# oswietlenie.net
KiCad netlist of a schematic drawn in EAGLE
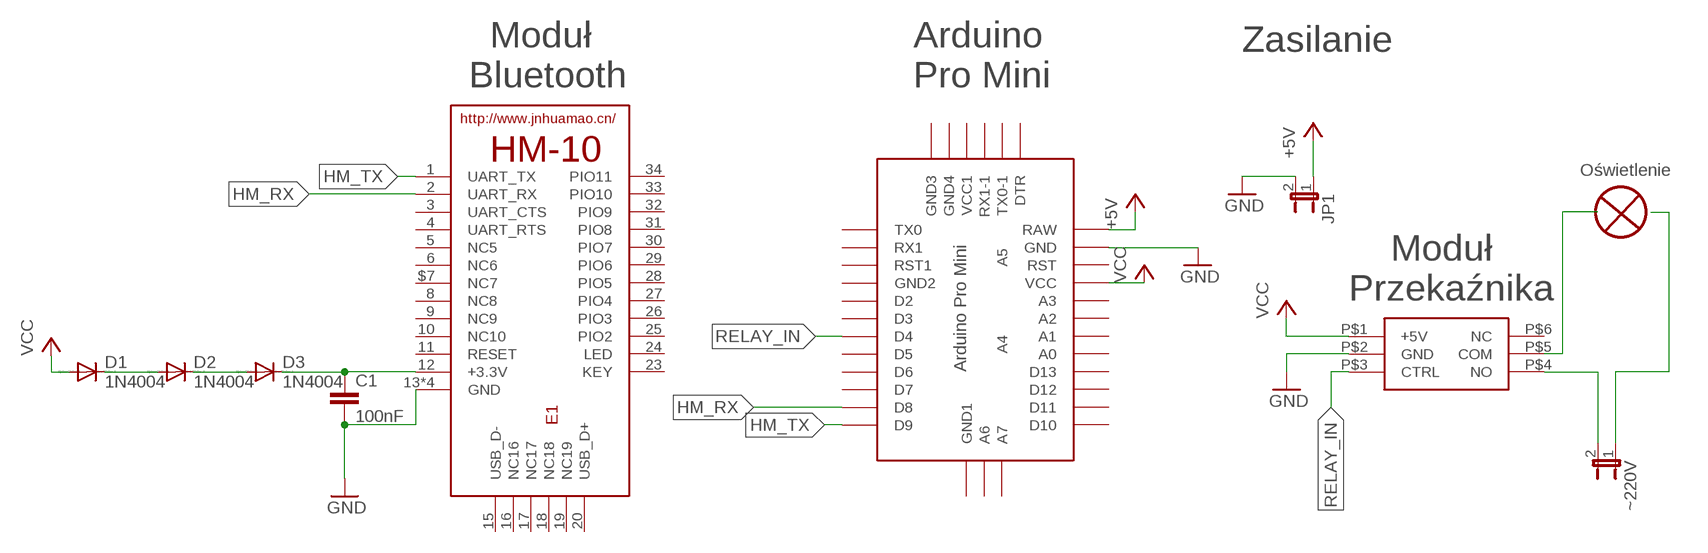
[diagram p0: schematic, sheet 1]

(export (version "E")
  (design (tool "Eeschema 10.0.6"))
  (components
    (comp (ref "C1")
      (value "100nF")
      (footprint "eagle-import:C025-024X044")
      (libsource (lib "eagle-import") (part "C-EU025-024X044"))
    )
    (comp (ref "D1")
      (value "1N4004")
      (footprint "eagle-import:DO41-10")
      (libsource (lib "eagle-import") (part "1N4004"))
    )
    (comp (ref "D2")
      (value "1N4004")
      (footprint "eagle-import:DO41-10")
      (libsource (lib "eagle-import") (part "1N4004"))
    )
    (comp (ref "D3")
      (value "1N4004")
      (footprint "eagle-import:DO41-10")
      (libsource (lib "eagle-import") (part "1N4004"))
    )
    (comp (ref "E1")
      (value "HM-10-BOARD")
      (footprint "eagle-import:26.9X13X2.2_BOARD")
      (libsource (lib "eagle-import") (part "HM-10-BOARD"))
    )
    (comp (ref "JP1")
      (value "JP1E")
      (footprint "eagle-import:JP1")
      (libsource (lib "eagle-import") (part "JP1E"))
    )
    (comp (ref "U$1")
      (value "ABK-PRO-MINI")
      (footprint "eagle-import:ABK-PRO-MINI")
      (libsource (lib "eagle-import") (part "ABK-PRO-MINI"))
    )
    (comp (ref "U$2")
      (value "G3VM-61E1")
      (footprint "eagle-import:G3VM-61E1")
      (libsource (lib "eagle-import") (part "G3VM-61E1"))
    )
    (comp (ref "~220V")
      (value "JP1E")
      (footprint "eagle-import:JP1")
      (libsource (lib "eagle-import") (part "JP1E"))
    )
  )
  (nets
    (net (code "1") (name "+5V") (class "Default")
      (node (ref "JP1") (pin "1") (pinfunction "1_1") (pintype "passive"))
      (node (ref "U$1") (pin "RAW") (pinfunction "RAW_RAW") (pintype "bidirectional"))
    )
    (net (code "2") (name "GND") (class "Default")
      (node (ref "C1") (pin "2") (pinfunction "2_2") (pintype "passive"))
      (node (ref "E1") (pin "13") (pinfunction "GND_13") (pintype "bidirectional"))
      (node (ref "E1") (pin "14") (pinfunction "GND_14") (pintype "bidirectional"))
      (node (ref "E1") (pin "21") (pinfunction "GND_21") (pintype "bidirectional"))
      (node (ref "E1") (pin "22") (pinfunction "GND_22") (pintype "bidirectional"))
      (node (ref "JP1") (pin "2") (pinfunction "2_2") (pintype "passive"))
      (node (ref "U$1") (pin "GND") (pinfunction "GND_GND") (pintype "bidirectional"))
      (node (ref "U$2") (pin "P$2") (pinfunction "GND_P$2") (pintype "bidirectional"))
    )
    (net (code "3") (name "HM_RX") (class "Default")
      (node (ref "E1") (pin "2") (pinfunction "UART_RX_2") (pintype "bidirectional"))
      (node (ref "U$1") (pin "D8") (pinfunction "D8_D8") (pintype "bidirectional"))
    )
    (net (code "4") (name "HM_TX") (class "Default")
      (node (ref "E1") (pin "1") (pinfunction "UART_TX_1") (pintype "bidirectional"))
      (node (ref "U$1") (pin "D9") (pinfunction "D9_D9") (pintype "bidirectional"))
    )
    (net (code "5") (name "Net-(D1-PadC)") (class "Default")
      (node (ref "D1") (pin "C") (pinfunction "C_C") (pintype "passive"))
      (node (ref "D2") (pin "A") (pinfunction "A_A") (pintype "passive"))
    )
    (net (code "6") (name "Net-(D2-PadC)") (class "Default")
      (node (ref "D2") (pin "C") (pinfunction "C_C") (pintype "passive"))
      (node (ref "D3") (pin "A") (pinfunction "A_A") (pintype "passive"))
    )
    (net (code "7") (name "Net-(E1-+3.3V)") (class "Default")
      (node (ref "C1") (pin "1") (pinfunction "1_1") (pintype "passive"))
      (node (ref "D3") (pin "C") (pinfunction "C_C") (pintype "passive"))
      (node (ref "E1") (pin "12") (pinfunction "+3.3V_12") (pintype "bidirectional"))
    )
    (net (code "8") (name "Net-(U$2-NO)") (class "Default")
      (node (ref "U$2") (pin "P$4") (pinfunction "NO_P$4") (pintype "bidirectional"))
      (node (ref "~220V") (pin "2") (pinfunction "2_2") (pintype "passive"))
    )
    (net (code "9") (name "RELAY_IN") (class "Default")
      (node (ref "U$1") (pin "D4") (pinfunction "D4_D4") (pintype "bidirectional"))
      (node (ref "U$2") (pin "P$3") (pinfunction "CTRL_P$3") (pintype "bidirectional"))
    )
    (net (code "10") (name "VCC") (class "Default")
      (node (ref "D1") (pin "A") (pinfunction "A_A") (pintype "passive"))
      (node (ref "U$1") (pin "VCC") (pinfunction "VCC_VCC") (pintype "bidirectional"))
      (node (ref "U$2") (pin "P$1") (pinfunction "+5V_P$1") (pintype "bidirectional"))
    )
    (net (code "11") (name "unconnected-(E1-KEY-Pad23)") (class "Default")
      (node (ref "E1") (pin "23") (pinfunction "KEY_23") (pintype "bidirectional"))
    )
    (net (code "12") (name "unconnected-(E1-LED-Pad24)") (class "Default")
      (node (ref "E1") (pin "24") (pinfunction "LED_24") (pintype "bidirectional"))
    )
    (net (code "13") (name "unconnected-(E1-NC5-Pad5)") (class "Default")
      (node (ref "E1") (pin "5") (pinfunction "NC5_5") (pintype "bidirectional"))
    )
    (net (code "14") (name "unconnected-(E1-NC6-Pad6)") (class "Default")
      (node (ref "E1") (pin "6") (pinfunction "NC6_6") (pintype "bidirectional"))
    )
    (net (code "15") (name "unconnected-(E1-NC7-Pad$7)") (class "Default")
      (node (ref "E1") (pin "$7") (pinfunction "NC7_$7") (pintype "bidirectional"))
    )
    (net (code "16") (name "unconnected-(E1-NC8-Pad8)") (class "Default")
      (node (ref "E1") (pin "8") (pinfunction "NC8_8") (pintype "bidirectional"))
    )
    (net (code "17") (name "unconnected-(E1-NC9-Pad9)") (class "Default")
      (node (ref "E1") (pin "9") (pinfunction "NC9_9") (pintype "bidirectional"))
    )
    (net (code "18") (name "unconnected-(E1-NC10-Pad10)") (class "Default")
      (node (ref "E1") (pin "10") (pinfunction "NC10_10") (pintype "bidirectional"))
    )
    (net (code "19") (name "unconnected-(E1-NC16-Pad16)") (class "Default")
      (node (ref "E1") (pin "16") (pinfunction "NC16_16") (pintype "bidirectional"))
    )
    (net (code "20") (name "unconnected-(E1-NC17-Pad17)") (class "Default")
      (node (ref "E1") (pin "17") (pinfunction "NC17_17") (pintype "bidirectional"))
    )
    (net (code "21") (name "unconnected-(E1-NC18-Pad18)") (class "Default")
      (node (ref "E1") (pin "18") (pinfunction "NC18_18") (pintype "bidirectional"))
    )
    (net (code "22") (name "unconnected-(E1-NC19-Pad19)") (class "Default")
      (node (ref "E1") (pin "19") (pinfunction "NC19_19") (pintype "bidirectional"))
    )
    (net (code "23") (name "unconnected-(E1-PIO2-Pad25)") (class "Default")
      (node (ref "E1") (pin "25") (pinfunction "PIO2_25") (pintype "bidirectional"))
    )
    (net (code "24") (name "unconnected-(E1-PIO3-Pad26)") (class "Default")
      (node (ref "E1") (pin "26") (pinfunction "PIO3_26") (pintype "bidirectional"))
    )
    (net (code "25") (name "unconnected-(E1-PIO4-Pad27)") (class "Default")
      (node (ref "E1") (pin "27") (pinfunction "PIO4_27") (pintype "bidirectional"))
    )
    (net (code "26") (name "unconnected-(E1-PIO5-Pad28)") (class "Default")
      (node (ref "E1") (pin "28") (pinfunction "PIO5_28") (pintype "bidirectional"))
    )
    (net (code "27") (name "unconnected-(E1-PIO6-Pad29)") (class "Default")
      (node (ref "E1") (pin "29") (pinfunction "PIO6_29") (pintype "bidirectional"))
    )
    (net (code "28") (name "unconnected-(E1-PIO7-Pad30)") (class "Default")
      (node (ref "E1") (pin "30") (pinfunction "PIO7_30") (pintype "bidirectional"))
    )
    (net (code "29") (name "unconnected-(E1-PIO8-Pad31)") (class "Default")
      (node (ref "E1") (pin "31") (pinfunction "PIO8_31") (pintype "bidirectional"))
    )
    (net (code "30") (name "unconnected-(E1-PIO9-Pad32)") (class "Default")
      (node (ref "E1") (pin "32") (pinfunction "PIO9_32") (pintype "bidirectional"))
    )
    (net (code "31") (name "unconnected-(E1-PIO10-Pad33)") (class "Default")
      (node (ref "E1") (pin "33") (pinfunction "PIO10_33") (pintype "bidirectional"))
    )
    (net (code "32") (name "unconnected-(E1-PIO11-Pad34)") (class "Default")
      (node (ref "E1") (pin "34") (pinfunction "PIO11_34") (pintype "bidirectional"))
    )
    (net (code "33") (name "unconnected-(E1-RESET-Pad11)") (class "Default")
      (node (ref "E1") (pin "11") (pinfunction "RESET_11") (pintype "bidirectional"))
    )
    (net (code "34") (name "unconnected-(E1-UART_CTS-Pad3)") (class "Default")
      (node (ref "E1") (pin "3") (pinfunction "UART_CTS_3") (pintype "bidirectional"))
    )
    (net (code "35") (name "unconnected-(E1-UART_RTS-Pad4)") (class "Default")
      (node (ref "E1") (pin "4") (pinfunction "UART_RTS_4") (pintype "bidirectional"))
    )
    (net (code "36") (name "unconnected-(E1-USB_D+-Pad20)") (class "Default")
      (node (ref "E1") (pin "20") (pinfunction "USB_D+_20") (pintype "bidirectional"))
    )
    (net (code "37") (name "unconnected-(E1-USB_D--Pad15)") (class "Default")
      (node (ref "E1") (pin "15") (pinfunction "USB_D-_15") (pintype "bidirectional"))
    )
    (net (code "38") (name "unconnected-(U$1-GND1-PadGND4)") (class "Default")
      (node (ref "U$1") (pin "GND4") (pinfunction "GND1_GND4") (pintype "bidirectional"))
    )
    (net (code "39") (name "unconnected-(U$1-GND2-PadGND1)") (class "Default")
      (node (ref "U$1") (pin "GND1") (pinfunction "GND2_GND1") (pintype "bidirectional"))
    )
    (net (code "40") (name "unconnected-(U$1-GND3-PadGND2)") (class "Default")
      (node (ref "U$1") (pin "GND2") (pinfunction "GND3_GND2") (pintype "bidirectional"))
    )
    (net (code "41") (name "unconnected-(U$1-GND4-PadGND3)") (class "Default")
      (node (ref "U$1") (pin "GND3") (pinfunction "GND4_GND3") (pintype "bidirectional"))
    )
    (net (code "42") (name "unconnected-(U$1-PadA0)") (class "Default")
      (node (ref "U$1") (pin "A0") (pinfunction "A0_A0") (pintype "bidirectional"))
    )
    (net (code "43") (name "unconnected-(U$1-PadA1)") (class "Default")
      (node (ref "U$1") (pin "A1") (pinfunction "A1_A1") (pintype "bidirectional"))
    )
    (net (code "44") (name "unconnected-(U$1-PadA2)") (class "Default")
      (node (ref "U$1") (pin "A2") (pinfunction "A2_A2") (pintype "bidirectional"))
    )
    (net (code "45") (name "unconnected-(U$1-PadA3)") (class "Default")
      (node (ref "U$1") (pin "A3") (pinfunction "A3_A3") (pintype "bidirectional"))
    )
    (net (code "46") (name "unconnected-(U$1-PadA4)") (class "Default")
      (node (ref "U$1") (pin "A4") (pinfunction "A4_A4") (pintype "bidirectional"))
    )
    (net (code "47") (name "unconnected-(U$1-PadA5)") (class "Default")
      (node (ref "U$1") (pin "A5") (pinfunction "A5_A5") (pintype "bidirectional"))
    )
    (net (code "48") (name "unconnected-(U$1-PadA6)") (class "Default")
      (node (ref "U$1") (pin "A6") (pinfunction "A6_A6") (pintype "bidirectional"))
    )
    (net (code "49") (name "unconnected-(U$1-PadA7)") (class "Default")
      (node (ref "U$1") (pin "A7") (pinfunction "A7_A7") (pintype "bidirectional"))
    )
    (net (code "50") (name "unconnected-(U$1-PadD2)") (class "Default")
      (node (ref "U$1") (pin "D2") (pinfunction "D2_D2") (pintype "bidirectional"))
    )
    (net (code "51") (name "unconnected-(U$1-PadD3)") (class "Default")
      (node (ref "U$1") (pin "D3") (pinfunction "D3_D3") (pintype "bidirectional"))
    )
    (net (code "52") (name "unconnected-(U$1-PadD5)") (class "Default")
      (node (ref "U$1") (pin "D5") (pinfunction "D5_D5") (pintype "bidirectional"))
    )
    (net (code "53") (name "unconnected-(U$1-PadD6)") (class "Default")
      (node (ref "U$1") (pin "D6") (pinfunction "D6_D6") (pintype "bidirectional"))
    )
    (net (code "54") (name "unconnected-(U$1-PadD7)") (class "Default")
      (node (ref "U$1") (pin "D7") (pinfunction "D7_D7") (pintype "bidirectional"))
    )
    (net (code "55") (name "unconnected-(U$1-PadD10)") (class "Default")
      (node (ref "U$1") (pin "D10") (pinfunction "D10_D10") (pintype "bidirectional"))
    )
    (net (code "56") (name "unconnected-(U$1-PadD11)") (class "Default")
      (node (ref "U$1") (pin "D11") (pinfunction "D11_D11") (pintype "bidirectional"))
    )
    (net (code "57") (name "unconnected-(U$1-PadD12)") (class "Default")
      (node (ref "U$1") (pin "D12") (pinfunction "D12_D12") (pintype "bidirectional"))
    )
    (net (code "58") (name "unconnected-(U$1-PadD13)") (class "Default")
      (node (ref "U$1") (pin "D13") (pinfunction "D13_D13") (pintype "bidirectional"))
    )
    (net (code "59") (name "unconnected-(U$1-PadDTR)") (class "Default")
      (node (ref "U$1") (pin "DTR") (pinfunction "DTR_DTR") (pintype "bidirectional"))
    )
    (net (code "60") (name "unconnected-(U$1-PadRST)") (class "Default")
      (node (ref "U$1") (pin "RST") (pinfunction "RST_RST") (pintype "bidirectional"))
    )
    (net (code "61") (name "unconnected-(U$1-PadRST1)") (class "Default")
      (node (ref "U$1") (pin "RST1") (pinfunction "RST1_RST1") (pintype "bidirectional"))
    )
    (net (code "62") (name "unconnected-(U$1-PadRX1)") (class "Default")
      (node (ref "U$1") (pin "RX1") (pinfunction "RX1_RX1") (pintype "bidirectional"))
    )
    (net (code "63") (name "unconnected-(U$1-PadRX1-1)") (class "Default")
      (node (ref "U$1") (pin "RX1-1") (pinfunction "RX1-1_RX1-1") (pintype "bidirectional"))
    )
    (net (code "64") (name "unconnected-(U$1-PadTX0)") (class "Default")
      (node (ref "U$1") (pin "TX0") (pinfunction "TX0_TX0") (pintype "bidirectional"))
    )
    (net (code "65") (name "unconnected-(U$1-PadTX0-1)") (class "Default")
      (node (ref "U$1") (pin "TX0-1") (pinfunction "TX0-1_TX0-1") (pintype "bidirectional"))
    )
    (net (code "66") (name "unconnected-(U$1-PadVCC1)") (class "Default")
      (node (ref "U$1") (pin "VCC1") (pinfunction "VCC1_VCC1") (pintype "bidirectional"))
    )
    (net (code "67") (name "unconnected-(U$2-COM-PadP$5)") (class "Default")
      (node (ref "U$2") (pin "P$5") (pinfunction "COM_P$5") (pintype "bidirectional"))
    )
    (net (code "68") (name "unconnected-(U$2-NC-PadP$6)") (class "Default")
      (node (ref "U$2") (pin "P$6") (pinfunction "NC_P$6") (pintype "bidirectional"))
    )
    (net (code "69") (name "unconnected-(~220V-Pad1)") (class "Default")
      (node (ref "~220V") (pin "1") (pinfunction "1_1") (pintype "passive"))
    )
  )
)
